# 8_Channel_Current_Sensor.net
KiCad netlist of a schematic drawn in EAGLE
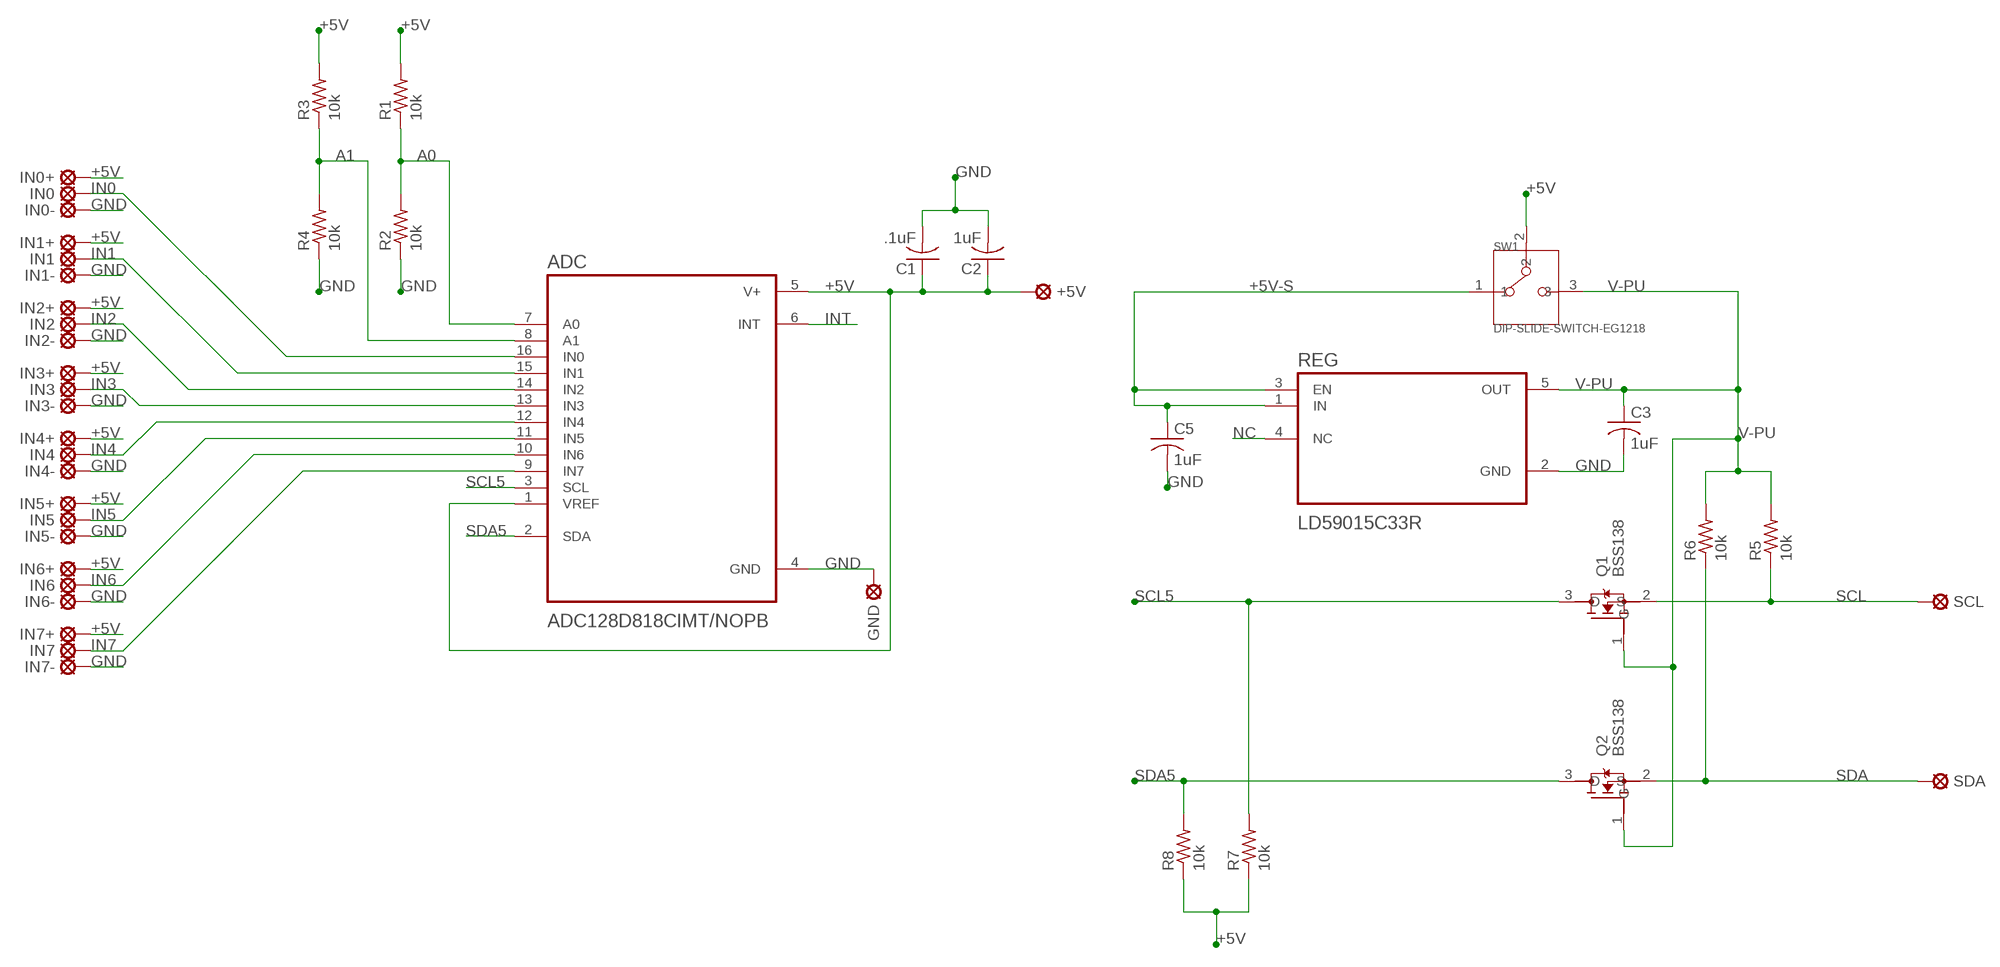
[diagram p0: schematic, sheet 1]

(export (version "E")
  (design (tool "Eeschema 10.0.6"))
  (components
    (comp (ref "+5V")
      (value "LSP10")
      (footprint "eagle-import:LSP10")
      (libsource (lib "eagle-import") (part "LSP10"))
    )
    (comp (ref "ADC")
      (value "ADC128D818CIMT/NOPB")
      (footprint "eagle-import:SOP65P640X120-16N")
      (fields (field (name "MF") "Texas Instruments"))
      (libsource (lib "eagle-import") (part "ADC128D818CIMT/NOPB"))
    )
    (comp (ref "C1")
      (value ".1uF")
      (footprint "eagle-import:C0603")
      (libsource (lib "eagle-import") (part "C-USC0603"))
    )
    (comp (ref "C2")
      (value "1uF")
      (footprint "eagle-import:C0603")
      (libsource (lib "eagle-import") (part "C-USC0603"))
    )
    (comp (ref "C3")
      (value "1uF")
      (footprint "eagle-import:C0603")
      (libsource (lib "eagle-import") (part "C-USC0603"))
    )
    (comp (ref "C5")
      (value "1uF")
      (footprint "eagle-import:C0603")
      (libsource (lib "eagle-import") (part "C-USC0603"))
    )
    (comp (ref "GND")
      (value "LSP10")
      (footprint "eagle-import:LSP10")
      (libsource (lib "eagle-import") (part "LSP10"))
    )
    (comp (ref "IN0")
      (value "LSP10")
      (footprint "eagle-import:LSP10")
      (libsource (lib "eagle-import") (part "LSP10"))
    )
    (comp (ref "IN0+")
      (value "LSP10")
      (footprint "eagle-import:LSP10")
      (libsource (lib "eagle-import") (part "LSP10"))
    )
    (comp (ref "IN0-")
      (value "LSP10")
      (footprint "eagle-import:LSP10")
      (libsource (lib "eagle-import") (part "LSP10"))
    )
    (comp (ref "IN1")
      (value "LSP10")
      (footprint "eagle-import:LSP10")
      (libsource (lib "eagle-import") (part "LSP10"))
    )
    (comp (ref "IN1+")
      (value "LSP10")
      (footprint "eagle-import:LSP10")
      (libsource (lib "eagle-import") (part "LSP10"))
    )
    (comp (ref "IN1-")
      (value "LSP10")
      (footprint "eagle-import:LSP10")
      (libsource (lib "eagle-import") (part "LSP10"))
    )
    (comp (ref "IN2")
      (value "LSP10")
      (footprint "eagle-import:LSP10")
      (libsource (lib "eagle-import") (part "LSP10"))
    )
    (comp (ref "IN2+")
      (value "LSP10")
      (footprint "eagle-import:LSP10")
      (libsource (lib "eagle-import") (part "LSP10"))
    )
    (comp (ref "IN2-")
      (value "LSP10")
      (footprint "eagle-import:LSP10")
      (libsource (lib "eagle-import") (part "LSP10"))
    )
    (comp (ref "IN3")
      (value "LSP10")
      (footprint "eagle-import:LSP10")
      (libsource (lib "eagle-import") (part "LSP10"))
    )
    (comp (ref "IN3+")
      (value "LSP10")
      (footprint "eagle-import:LSP10")
      (libsource (lib "eagle-import") (part "LSP10"))
    )
    (comp (ref "IN3-")
      (value "LSP10")
      (footprint "eagle-import:LSP10")
      (libsource (lib "eagle-import") (part "LSP10"))
    )
    (comp (ref "IN4")
      (value "LSP10")
      (footprint "eagle-import:LSP10")
      (libsource (lib "eagle-import") (part "LSP10"))
    )
    (comp (ref "IN4+")
      (value "LSP10")
      (footprint "eagle-import:LSP10")
      (libsource (lib "eagle-import") (part "LSP10"))
    )
    (comp (ref "IN4-")
      (value "LSP10")
      (footprint "eagle-import:LSP10")
      (libsource (lib "eagle-import") (part "LSP10"))
    )
    (comp (ref "IN5")
      (value "LSP10")
      (footprint "eagle-import:LSP10")
      (libsource (lib "eagle-import") (part "LSP10"))
    )
    (comp (ref "IN5+")
      (value "LSP10")
      (footprint "eagle-import:LSP10")
      (libsource (lib "eagle-import") (part "LSP10"))
    )
    (comp (ref "IN5-")
      (value "LSP10")
      (footprint "eagle-import:LSP10")
      (libsource (lib "eagle-import") (part "LSP10"))
    )
    (comp (ref "IN6")
      (value "LSP10")
      (footprint "eagle-import:LSP10")
      (libsource (lib "eagle-import") (part "LSP10"))
    )
    (comp (ref "IN6+")
      (value "LSP10")
      (footprint "eagle-import:LSP10")
      (libsource (lib "eagle-import") (part "LSP10"))
    )
    (comp (ref "IN6-")
      (value "LSP10")
      (footprint "eagle-import:LSP10")
      (libsource (lib "eagle-import") (part "LSP10"))
    )
    (comp (ref "IN7")
      (value "LSP10")
      (footprint "eagle-import:LSP10")
      (libsource (lib "eagle-import") (part "LSP10"))
    )
    (comp (ref "IN7+")
      (value "LSP10")
      (footprint "eagle-import:LSP10")
      (libsource (lib "eagle-import") (part "LSP10"))
    )
    (comp (ref "IN7-")
      (value "LSP10")
      (footprint "eagle-import:LSP10")
      (libsource (lib "eagle-import") (part "LSP10"))
    )
    (comp (ref "Q1")
      (value "BSS138")
      (footprint "eagle-import:SOT95P240X120-3N")
      (fields (field (name "MF") "ON Semiconductor"))
      (libsource (lib "eagle-import") (part "BSS138"))
    )
    (comp (ref "Q2")
      (value "BSS138")
      (footprint "eagle-import:SOT95P240X120-3N")
      (fields (field (name "MF") "ON Semiconductor"))
      (libsource (lib "eagle-import") (part "BSS138"))
    )
    (comp (ref "R1")
      (value "10k")
      (footprint "eagle-import:R0603")
      (libsource (lib "eagle-import") (part "R-US_R0603"))
    )
    (comp (ref "R2")
      (value "10k")
      (footprint "eagle-import:R0603")
      (libsource (lib "eagle-import") (part "R-US_R0603"))
    )
    (comp (ref "R3")
      (value "10k")
      (footprint "eagle-import:R0603")
      (libsource (lib "eagle-import") (part "R-US_R0603"))
    )
    (comp (ref "R4")
      (value "10k")
      (footprint "eagle-import:R0603")
      (libsource (lib "eagle-import") (part "R-US_R0603"))
    )
    (comp (ref "R5")
      (value "10k")
      (footprint "eagle-import:R0603")
      (libsource (lib "eagle-import") (part "R-US_R0603"))
    )
    (comp (ref "R6")
      (value "10k")
      (footprint "eagle-import:R0603")
      (libsource (lib "eagle-import") (part "R-US_R0603"))
    )
    (comp (ref "R7")
      (value "10k")
      (footprint "eagle-import:R0603")
      (libsource (lib "eagle-import") (part "R-US_R0603"))
    )
    (comp (ref "R8")
      (value "10k")
      (footprint "eagle-import:R0603")
      (libsource (lib "eagle-import") (part "R-US_R0603"))
    )
    (comp (ref "REG")
      (value "LD59015C33R")
      (footprint "eagle-import:SOT65P210X110-5N")
      (fields (field (name "MF") "STMicroelectronics"))
      (libsource (lib "eagle-import") (part "LD59015C33R"))
    )
    (comp (ref "SCL")
      (value "LSP10")
      (footprint "eagle-import:LSP10")
      (libsource (lib "eagle-import") (part "LSP10"))
    )
    (comp (ref "SDA")
      (value "LSP10")
      (footprint "eagle-import:LSP10")
      (libsource (lib "eagle-import") (part "LSP10"))
    )
    (comp (ref "SW1")
      (value "DIP-SLIDE-SWITCH-EG1218")
      (footprint "eagle-import:SW3-2.5-11.6X4.0X5.4+2.0MM")
      (fields (field (name "MF") "E-Switch") (field (name "MP") "EG1218"))
      (libsource (lib "eagle-import") (part "DIP-SLIDE-SWITCH-EG1218"))
    )
  )
  (nets
    (net (code "1") (name "/+5V") (class "Default")
      (node (ref "+5V") (pin "MP") (pinfunction "MP_MP") (pintype "passive"))
      (node (ref "ADC") (pin "1") (pinfunction "VREF_1") (pintype "input"))
      (node (ref "ADC") (pin "5") (pinfunction "V+_5") (pintype "power_in"))
      (node (ref "C1") (pin "1") (pinfunction "1_1") (pintype "passive"))
      (node (ref "C2") (pin "1") (pinfunction "1_1") (pintype "passive"))
      (node (ref "IN0+") (pin "MP") (pinfunction "MP_MP") (pintype "passive"))
      (node (ref "IN1+") (pin "MP") (pinfunction "MP_MP") (pintype "passive"))
      (node (ref "IN2+") (pin "MP") (pinfunction "MP_MP") (pintype "passive"))
      (node (ref "IN3+") (pin "MP") (pinfunction "MP_MP") (pintype "passive"))
      (node (ref "IN4+") (pin "MP") (pinfunction "MP_MP") (pintype "passive"))
      (node (ref "IN5+") (pin "MP") (pinfunction "MP_MP") (pintype "passive"))
      (node (ref "IN6+") (pin "MP") (pinfunction "MP_MP") (pintype "passive"))
      (node (ref "IN7+") (pin "MP") (pinfunction "MP_MP") (pintype "passive"))
      (node (ref "R1") (pin "2") (pinfunction "2_2") (pintype "passive"))
      (node (ref "R3") (pin "2") (pinfunction "2_2") (pintype "passive"))
      (node (ref "R7") (pin "1") (pinfunction "1_1") (pintype "passive"))
      (node (ref "R8") (pin "1") (pinfunction "1_1") (pintype "passive"))
      (node (ref "SW1") (pin "2") (pinfunction "2_2") (pintype "bidirectional"))
    )
    (net (code "2") (name "/+5V-S") (class "Default")
      (node (ref "C5") (pin "1") (pinfunction "1_1") (pintype "passive"))
      (node (ref "REG") (pin "1") (pinfunction "IN_1") (pintype "input"))
      (node (ref "REG") (pin "3") (pinfunction "EN_3") (pintype "input"))
      (node (ref "SW1") (pin "1") (pinfunction "1_1") (pintype "bidirectional"))
    )
    (net (code "3") (name "/A0") (class "Default")
      (node (ref "ADC") (pin "7") (pinfunction "A0_7") (pintype "input"))
      (node (ref "R1") (pin "1") (pinfunction "1_1") (pintype "passive"))
      (node (ref "R2") (pin "2") (pinfunction "2_2") (pintype "passive"))
    )
    (net (code "4") (name "/A1") (class "Default")
      (node (ref "ADC") (pin "8") (pinfunction "A1_8") (pintype "input"))
      (node (ref "R3") (pin "1") (pinfunction "1_1") (pintype "passive"))
      (node (ref "R4") (pin "2") (pinfunction "2_2") (pintype "passive"))
    )
    (net (code "5") (name "/GND") (class "Default")
      (node (ref "ADC") (pin "4") (pinfunction "GND_4") (pintype "power_in"))
      (node (ref "C1") (pin "2") (pinfunction "2_2") (pintype "passive"))
      (node (ref "C2") (pin "2") (pinfunction "2_2") (pintype "passive"))
      (node (ref "C3") (pin "2") (pinfunction "2_2") (pintype "passive"))
      (node (ref "C5") (pin "2") (pinfunction "2_2") (pintype "passive"))
      (node (ref "GND") (pin "MP") (pinfunction "MP_MP") (pintype "passive"))
      (node (ref "IN0-") (pin "MP") (pinfunction "MP_MP") (pintype "passive"))
      (node (ref "IN1-") (pin "MP") (pinfunction "MP_MP") (pintype "passive"))
      (node (ref "IN2-") (pin "MP") (pinfunction "MP_MP") (pintype "passive"))
      (node (ref "IN3-") (pin "MP") (pinfunction "MP_MP") (pintype "passive"))
      (node (ref "IN4-") (pin "MP") (pinfunction "MP_MP") (pintype "passive"))
      (node (ref "IN5-") (pin "MP") (pinfunction "MP_MP") (pintype "passive"))
      (node (ref "IN6-") (pin "MP") (pinfunction "MP_MP") (pintype "passive"))
      (node (ref "IN7-") (pin "MP") (pinfunction "MP_MP") (pintype "passive"))
      (node (ref "R2") (pin "1") (pinfunction "1_1") (pintype "passive"))
      (node (ref "R4") (pin "1") (pinfunction "1_1") (pintype "passive"))
      (node (ref "REG") (pin "2") (pinfunction "GND_2") (pintype "power_in"))
    )
    (net (code "6") (name "/IN0") (class "Default")
      (node (ref "ADC") (pin "16") (pinfunction "IN0_16") (pintype "input"))
      (node (ref "IN0") (pin "MP") (pinfunction "MP_MP") (pintype "passive"))
    )
    (net (code "7") (name "/IN1") (class "Default")
      (node (ref "ADC") (pin "15") (pinfunction "IN1_15") (pintype "input"))
      (node (ref "IN1") (pin "MP") (pinfunction "MP_MP") (pintype "passive"))
    )
    (net (code "8") (name "/IN2") (class "Default")
      (node (ref "ADC") (pin "14") (pinfunction "IN2_14") (pintype "input"))
      (node (ref "IN2") (pin "MP") (pinfunction "MP_MP") (pintype "passive"))
    )
    (net (code "9") (name "/IN3") (class "Default")
      (node (ref "ADC") (pin "13") (pinfunction "IN3_13") (pintype "input"))
      (node (ref "IN3") (pin "MP") (pinfunction "MP_MP") (pintype "passive"))
    )
    (net (code "10") (name "/IN4") (class "Default")
      (node (ref "ADC") (pin "12") (pinfunction "IN4_12") (pintype "input"))
      (node (ref "IN4") (pin "MP") (pinfunction "MP_MP") (pintype "passive"))
    )
    (net (code "11") (name "/IN5") (class "Default")
      (node (ref "ADC") (pin "11") (pinfunction "IN5_11") (pintype "input"))
      (node (ref "IN5") (pin "MP") (pinfunction "MP_MP") (pintype "passive"))
    )
    (net (code "12") (name "/IN6") (class "Default")
      (node (ref "ADC") (pin "10") (pinfunction "IN6_10") (pintype "input"))
      (node (ref "IN6") (pin "MP") (pinfunction "MP_MP") (pintype "passive"))
    )
    (net (code "13") (name "/IN7") (class "Default")
      (node (ref "ADC") (pin "9") (pinfunction "IN7_9") (pintype "input"))
      (node (ref "IN7") (pin "MP") (pinfunction "MP_MP") (pintype "passive"))
    )
    (net (code "14") (name "/INT") (class "Default")
      (node (ref "ADC") (pin "6") (pinfunction "INT_6") (pintype "output"))
    )
    (net (code "15") (name "/NC") (class "Default")
      (node (ref "REG") (pin "4") (pinfunction "NC_4") (pintype "bidirectional"))
    )
    (net (code "16") (name "/SCL") (class "Default")
      (node (ref "Q1") (pin "2") (pinfunction "S_2") (pintype "passive"))
      (node (ref "R5") (pin "1") (pinfunction "1_1") (pintype "passive"))
      (node (ref "SCL") (pin "MP") (pinfunction "MP_MP") (pintype "passive"))
    )
    (net (code "17") (name "/SCL5") (class "Default")
      (node (ref "ADC") (pin "3") (pinfunction "SCL_3") (pintype "input"))
      (node (ref "Q1") (pin "3") (pinfunction "D_3") (pintype "passive"))
      (node (ref "R7") (pin "2") (pinfunction "2_2") (pintype "passive"))
    )
    (net (code "18") (name "/SDA") (class "Default")
      (node (ref "Q2") (pin "2") (pinfunction "S_2") (pintype "passive"))
      (node (ref "R6") (pin "1") (pinfunction "1_1") (pintype "passive"))
      (node (ref "SDA") (pin "MP") (pinfunction "MP_MP") (pintype "passive"))
    )
    (net (code "19") (name "/SDA5") (class "Default")
      (node (ref "ADC") (pin "2") (pinfunction "SDA_2") (pintype "bidirectional"))
      (node (ref "Q2") (pin "3") (pinfunction "D_3") (pintype "passive"))
      (node (ref "R8") (pin "2") (pinfunction "2_2") (pintype "passive"))
    )
    (net (code "20") (name "/V-PU") (class "Default")
      (node (ref "C3") (pin "1") (pinfunction "1_1") (pintype "passive"))
      (node (ref "Q1") (pin "1") (pinfunction "G_1") (pintype "passive"))
      (node (ref "Q2") (pin "1") (pinfunction "G_1") (pintype "passive"))
      (node (ref "R5") (pin "2") (pinfunction "2_2") (pintype "passive"))
      (node (ref "R6") (pin "2") (pinfunction "2_2") (pintype "passive"))
      (node (ref "REG") (pin "5") (pinfunction "OUT_5") (pintype "output"))
      (node (ref "SW1") (pin "3") (pinfunction "3_3") (pintype "bidirectional"))
    )
  )
)
